# MLA_v1-02Dec2014.net
KiCad netlist of a schematic drawn in Altium Designer
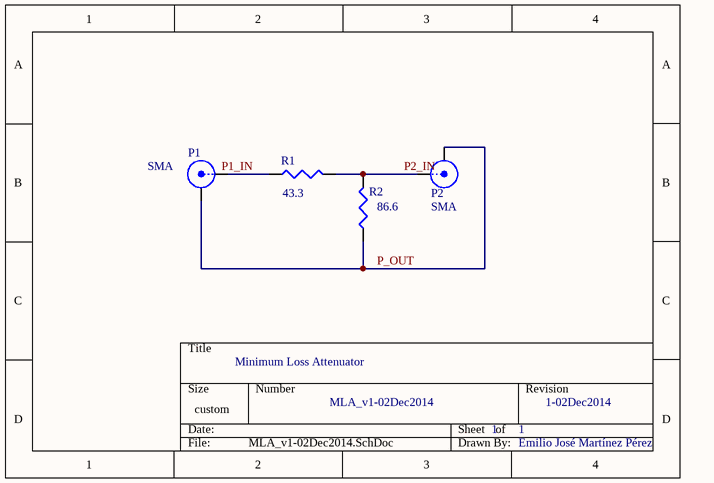
[diagram p0: MLA_v1-02Dec2014.SchDoc]

(export (version "E")
  (design (tool "Eeschema 10.0.6"))
  (components
    (comp (ref "P1")
      (value "SMA")
      (footprint "SMA")
      (fields (field (name "PUBLISHER") "Altium Limited"))
      (libsource (lib "Miscellaneous Connectors") (part "SMA"))
    )
    (comp (ref "P2")
      (value "SMA")
      (footprint "SMA")
      (fields (field (name "PUBLISHER") "Altium Limited"))
      (libsource (lib "Miscellaneous Connectors") (part "SMA"))
    )
    (comp (ref "R1")
      (value "43.3")
      (footprint "J1-0603")
      (description "Resistor")
      (fields (field (name "PUBLISHER") "Altium Limited"))
      (libsource (lib "Miscellaneous Devices") (part "Res3"))
    )
    (comp (ref "R2")
      (value "86.6")
      (footprint "J1-0603")
      (description "Resistor")
      (fields (field (name "PUBLISHER") "Altium Limited"))
      (libsource (lib "Miscellaneous Devices") (part "Res3"))
    )
  )
  (nets
    (net (code "2") (name "/P2_IN") (class "Default")
      (node (ref "P2") (pin "1") (pinfunction "X_1") (pintype "passive"))
      (node (ref "R1") (pin "2") (pinfunction "2_2") (pintype "passive"))
      (node (ref "R2") (pin "2") (pinfunction "2_2") (pintype "passive"))
    )
    (net (code "3") (name "/P_OUT") (class "Default")
      (node (ref "P1") (pin "2") (pinfunction "Y_2") (pintype "passive"))
      (node (ref "P2") (pin "2") (pinfunction "Y_2") (pintype "passive"))
      (node (ref "R2") (pin "1") (pinfunction "1_1") (pintype "passive"))
    )
    (net (code "4") (name "Net-(P1-X)") (class "Default")
      (node (ref "P1") (pin "1") (pinfunction "X_1") (pintype "passive"))
      (node (ref "R1") (pin "1") (pinfunction "1_1") (pintype "passive"))
    )
  )
)
